# eMMC_SD.net
KiCad netlist of a schematic drawn in Altium Designer
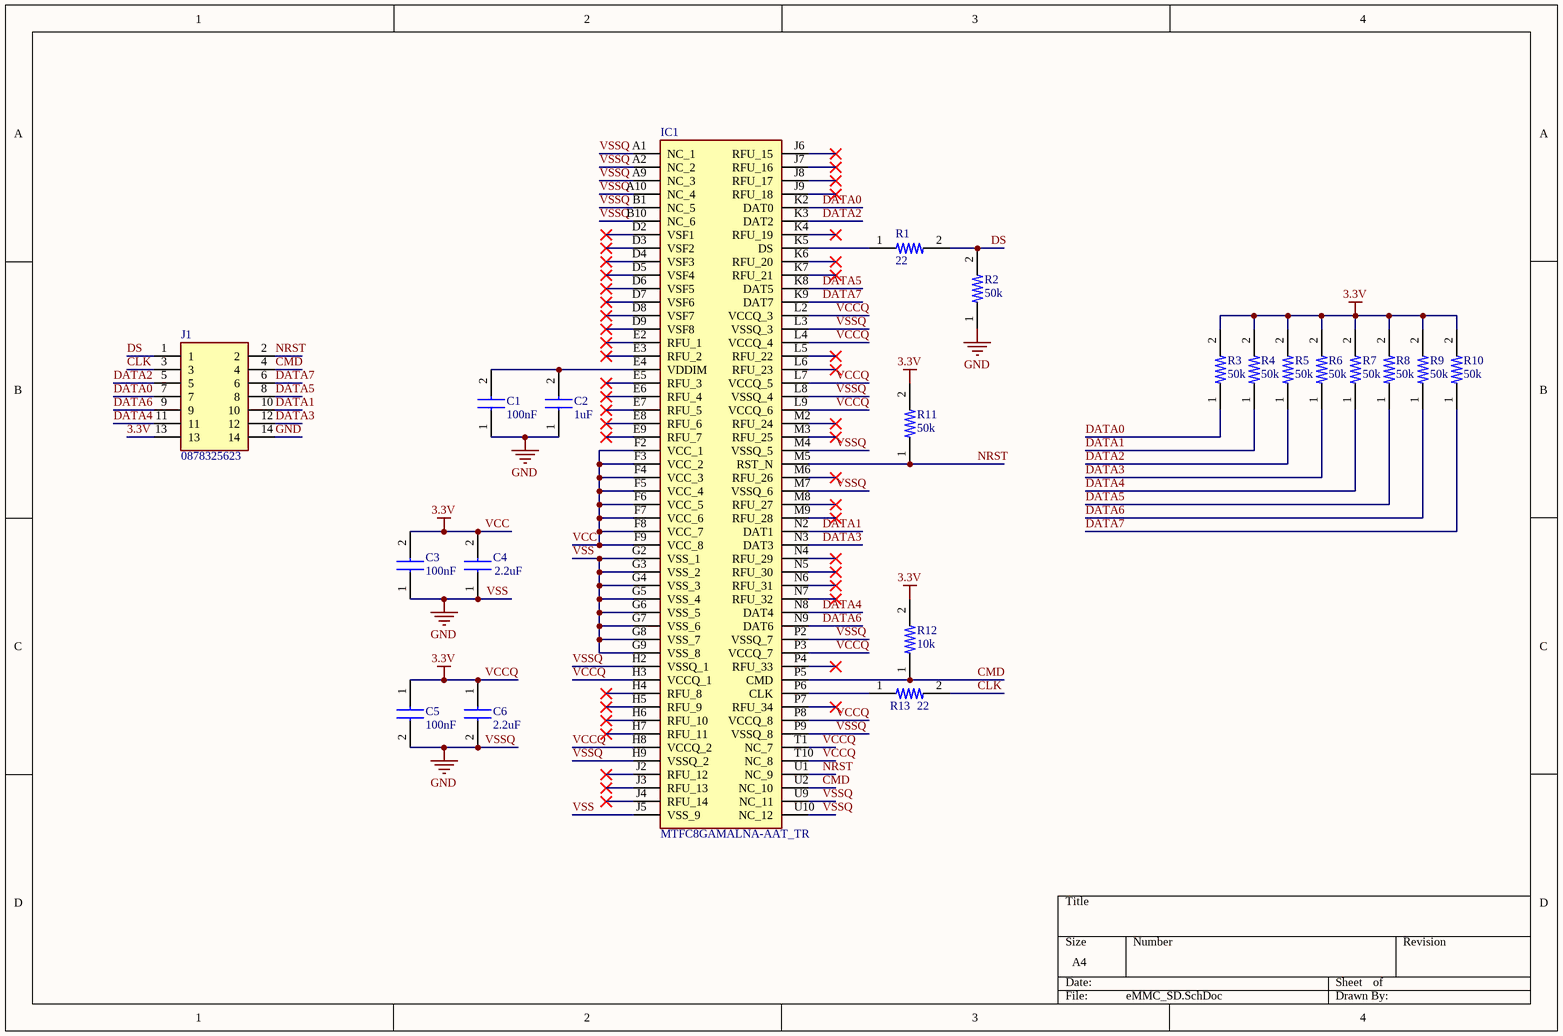
[diagram p0: eMMC_SD.SchDoc]

(export (version "E")
  (design (tool "Eeschema 10.0.6"))
  (components
    (comp (ref "C1")
      (value "100nF")
      (footprint "CAPC2012X140N")
      (description "Capacitor\r\n\r\nKAM21BR71H104JT")
      (fields
        (field (name "MANUFACTURER_PART_NUMBER") "08055C105K4Z2A")
        (field (name "MOUSER PART NUMBER") "581-08055C105K4Z2A")
      )
      (libsource (lib "TLMoto - Eletrónica") (part "MCAST21GSB7105MTNB25"))
    )
    (comp (ref "C2")
      (value "1uF")
      (footprint "CAPC2012X140N")
      (description "Capacitor\r\n\r\n08055C105K4Z2A")
      (fields
        (field (name "MANUFACTURER_PART_NUMBER") "08055C105K4Z2A")
        (field (name "MOUSER PART NUMBER") "581-08055C105K4Z2A")
      )
      (libsource (lib "TLMoto - Eletrónica") (part "MCAST21GSB7105MTNB25"))
    )
    (comp (ref "C3")
      (value "100nF")
      (footprint "CAPC2012X140N")
      (description "Capacitor\r\n\r\nKAM21BR71H104JT")
      (fields
        (field (name "MANUFACTURER_PART_NUMBER") "08055C105K4Z2A")
        (field (name "MOUSER PART NUMBER") "581-08055C105K4Z2A")
      )
      (libsource (lib "TLMoto - Eletrónica") (part "MCAST21GSB7105MTNB25"))
    )
    (comp (ref "C4")
      (value "2.2uF")
      (footprint "CAPC2012X140N")
      (description "Capacitor\r\n\r\nC2012X7R1E225K125AB")
      (fields
        (field (name "MANUFACTURER_PART_NUMBER") "08055C105K4Z2A")
        (field (name "MOUSER PART NUMBER") "581-08055C105K4Z2A")
      )
      (libsource (lib "TLMoto - Eletrónica") (part "MCAST21GSB7105MTNB25"))
    )
    (comp (ref "C5")
      (value "100nF")
      (footprint "CAPC2012X140N")
      (description "Capacitor\r\n\r\nKAM21BR71H104JT")
      (fields
        (field (name "MANUFACTURER_PART_NUMBER") "08055C105K4Z2A")
        (field (name "MOUSER PART NUMBER") "581-08055C105K4Z2A")
      )
      (libsource (lib "TLMoto - Eletrónica") (part "MCAST21GSB7105MTNB25"))
    )
    (comp (ref "C6")
      (value "2.2uF")
      (footprint "CAPC2012X140N")
      (description "Capacitor\r\n\r\nC2012X7R1E225K125AB")
      (fields
        (field (name "MANUFACTURER_PART_NUMBER") "08055C105K4Z2A")
        (field (name "MOUSER PART NUMBER") "581-08055C105K4Z2A")
      )
      (libsource (lib "TLMoto - Eletrónica") (part "MCAST21GSB7105MTNB25"))
    )
    (comp (ref "IC1")
      (value "MTFC8GAMALNA-AAT_TR")
      (footprint "BGA100C100P10X17_1400X1800X120")
      (description "Multi Media Card Controller and NAND Flash e.MMC Memory")
      (fields
        (field (name "MANUFACTURER_PART_NUMBER") "MTFC8GAMALNA-AAT TR")
        (field (name "MOUSER PART NUMBER") "340-354324-REEL")
      )
      (libsource (lib "TLMoto - Eletrónica") (part "MTFC8GAMALNA-AAT_TR"))
    )
    (comp (ref "J1")
      (value "0878325623")
      (footprint "SamacSys:0878325623")
      (description "Connector")
      (libsource (lib "*") (part "0878325623"))
    )
    (comp (ref "R1")
      (value "22")
      (footprint "RESC2012X60N")
      (description "Resistor")
      (fields (field (name "SOURCE") "MotoLibrary.SchLib"))
      (libsource (lib "TLMoto - Eletrónica") (part "R 0805 (2012)"))
    )
    (comp (ref "R2")
      (value "50k")
      (footprint "RESC2012X60N")
      (description "Resistor")
      (fields (field (name "SOURCE") "MotoLibrary.SchLib"))
      (libsource (lib "TLMoto - Eletrónica") (part "R 0805 (2012)"))
    )
    (comp (ref "R3")
      (value "50k")
      (footprint "RESC2012X60N")
      (description "Resistor")
      (fields (field (name "SOURCE") "MotoLibrary.SchLib"))
      (libsource (lib "TLMoto - Eletrónica") (part "R 0805 (2012)"))
    )
    (comp (ref "R4")
      (value "50k")
      (footprint "RESC2012X60N")
      (description "Resistor")
      (fields (field (name "SOURCE") "MotoLibrary.SchLib"))
      (libsource (lib "TLMoto - Eletrónica") (part "R 0805 (2012)"))
    )
    (comp (ref "R5")
      (value "50k")
      (footprint "RESC2012X60N")
      (description "Resistor")
      (fields (field (name "SOURCE") "MotoLibrary.SchLib"))
      (libsource (lib "TLMoto - Eletrónica") (part "R 0805 (2012)"))
    )
    (comp (ref "R6")
      (value "50k")
      (footprint "RESC2012X60N")
      (description "Resistor")
      (fields (field (name "SOURCE") "MotoLibrary.SchLib"))
      (libsource (lib "TLMoto - Eletrónica") (part "R 0805 (2012)"))
    )
    (comp (ref "R7")
      (value "50k")
      (footprint "RESC2012X60N")
      (description "Resistor")
      (fields (field (name "SOURCE") "MotoLibrary.SchLib"))
      (libsource (lib "TLMoto - Eletrónica") (part "R 0805 (2012)"))
    )
    (comp (ref "R8")
      (value "50k")
      (footprint "RESC2012X60N")
      (description "Resistor")
      (fields (field (name "SOURCE") "MotoLibrary.SchLib"))
      (libsource (lib "TLMoto - Eletrónica") (part "R 0805 (2012)"))
    )
    (comp (ref "R9")
      (value "50k")
      (footprint "RESC2012X60N")
      (description "Resistor")
      (fields (field (name "SOURCE") "MotoLibrary.SchLib"))
      (libsource (lib "TLMoto - Eletrónica") (part "R 0805 (2012)"))
    )
    (comp (ref "R10")
      (value "50k")
      (footprint "RESC2012X60N")
      (description "Resistor")
      (fields (field (name "SOURCE") "MotoLibrary.SchLib"))
      (libsource (lib "TLMoto - Eletrónica") (part "R 0805 (2012)"))
    )
    (comp (ref "R11")
      (value "50k")
      (footprint "RESC2012X60N")
      (description "Resistor")
      (fields (field (name "SOURCE") "MotoLibrary.SchLib"))
      (libsource (lib "TLMoto - Eletrónica") (part "R 0805 (2012)"))
    )
    (comp (ref "R12")
      (value "10k")
      (footprint "RESC2012X60N")
      (description "Resistor")
      (fields (field (name "SOURCE") "MotoLibrary.SchLib"))
      (libsource (lib "TLMoto - Eletrónica") (part "R 0805 (2012)"))
    )
    (comp (ref "R13")
      (value "22")
      (footprint "RESC2012X60N")
      (description "Resistor")
      (fields (field (name "SOURCE") "MotoLibrary.SchLib"))
      (libsource (lib "TLMoto - Eletrónica") (part "R 0805 (2012)"))
    )
  )
  (nets
    (net (code "1") (name "/CLK") (class "Default")
      (node (ref "J1") (pin "3") (pinfunction "3_3") (pintype "passive"))
      (node (ref "R13") (pin "2") (pinfunction "2_2") (pintype "passive"))
    )
    (net (code "2") (name "/CMD") (class "Default")
      (node (ref "IC1") (pin "P5") (pinfunction "CMD_P5") (pintype "passive"))
      (node (ref "IC1") (pin "U2") (pinfunction "NC_10_U2") (pintype "passive"))
      (node (ref "J1") (pin "4") (pinfunction "4_4") (pintype "passive"))
      (node (ref "R12") (pin "1") (pinfunction "1_1") (pintype "passive"))
    )
    (net (code "3") (name "/DATA0") (class "Default")
      (node (ref "IC1") (pin "K2") (pinfunction "DAT0_K2") (pintype "passive"))
      (node (ref "J1") (pin "7") (pinfunction "7_7") (pintype "passive"))
      (node (ref "R3") (pin "1") (pinfunction "1_1") (pintype "passive"))
    )
    (net (code "4") (name "/DATA1") (class "Default")
      (node (ref "IC1") (pin "N2") (pinfunction "DAT1_N2") (pintype "passive"))
      (node (ref "J1") (pin "10") (pinfunction "10_10") (pintype "passive"))
      (node (ref "R4") (pin "1") (pinfunction "1_1") (pintype "passive"))
    )
    (net (code "5") (name "/DATA2") (class "Default")
      (node (ref "IC1") (pin "K3") (pinfunction "DAT2_K3") (pintype "passive"))
      (node (ref "J1") (pin "5") (pinfunction "5_5") (pintype "passive"))
      (node (ref "R5") (pin "1") (pinfunction "1_1") (pintype "passive"))
    )
    (net (code "6") (name "/DATA3") (class "Default")
      (node (ref "IC1") (pin "N3") (pinfunction "DAT3_N3") (pintype "passive"))
      (node (ref "J1") (pin "12") (pinfunction "12_12") (pintype "passive"))
      (node (ref "R6") (pin "1") (pinfunction "1_1") (pintype "passive"))
    )
    (net (code "7") (name "/DATA4") (class "Default")
      (node (ref "IC1") (pin "N8") (pinfunction "DAT4_N8") (pintype "passive"))
      (node (ref "J1") (pin "11") (pinfunction "11_11") (pintype "passive"))
      (node (ref "R7") (pin "1") (pinfunction "1_1") (pintype "passive"))
    )
    (net (code "8") (name "/DATA5") (class "Default")
      (node (ref "IC1") (pin "K8") (pinfunction "DAT5_K8") (pintype "passive"))
      (node (ref "J1") (pin "8") (pinfunction "8_8") (pintype "passive"))
      (node (ref "R8") (pin "1") (pinfunction "1_1") (pintype "passive"))
    )
    (net (code "9") (name "/DATA6") (class "Default")
      (node (ref "IC1") (pin "N9") (pinfunction "DAT6_N9") (pintype "passive"))
      (node (ref "J1") (pin "9") (pinfunction "9_9") (pintype "passive"))
      (node (ref "R9") (pin "1") (pinfunction "1_1") (pintype "passive"))
    )
    (net (code "10") (name "/DATA7") (class "Default")
      (node (ref "IC1") (pin "K9") (pinfunction "DAT7_K9") (pintype "passive"))
      (node (ref "J1") (pin "6") (pinfunction "6_6") (pintype "passive"))
      (node (ref "R10") (pin "1") (pinfunction "1_1") (pintype "passive"))
    )
    (net (code "11") (name "/DS") (class "Default")
      (node (ref "J1") (pin "1") (pinfunction "1_1") (pintype "passive"))
      (node (ref "R1") (pin "2") (pinfunction "2_2") (pintype "passive"))
      (node (ref "R2") (pin "2") (pinfunction "2_2") (pintype "passive"))
    )
    (net (code "12") (name "/NRST") (class "Default")
      (node (ref "IC1") (pin "M5") (pinfunction "RST_N_M5") (pintype "passive"))
      (node (ref "IC1") (pin "U1") (pinfunction "NC_9_U1") (pintype "passive"))
      (node (ref "J1") (pin "2") (pinfunction "2_2") (pintype "passive"))
      (node (ref "R11") (pin "1") (pinfunction "1_1") (pintype "passive"))
    )
    (net (code "13") (name "3.3V") (class "Default")
      (node (ref "C3") (pin "2") (pinfunction "2_2") (pintype "passive"))
      (node (ref "C4") (pin "2") (pinfunction "2_2") (pintype "passive"))
      (node (ref "C5") (pin "1") (pinfunction "1_1") (pintype "passive"))
      (node (ref "C6") (pin "1") (pinfunction "1_1") (pintype "passive"))
      (node (ref "IC1") (pin "F2") (pinfunction "VCC_1_F2") (pintype "passive"))
      (node (ref "IC1") (pin "F3") (pinfunction "VCC_2_F3") (pintype "passive"))
      (node (ref "IC1") (pin "F4") (pinfunction "VCC_3_F4") (pintype "passive"))
      (node (ref "IC1") (pin "F5") (pinfunction "VCC_4_F5") (pintype "passive"))
      (node (ref "IC1") (pin "F6") (pinfunction "VCC_5_F6") (pintype "passive"))
      (node (ref "IC1") (pin "F7") (pinfunction "VCC_6_F7") (pintype "passive"))
      (node (ref "IC1") (pin "F8") (pinfunction "VCC_7_F8") (pintype "passive"))
      (node (ref "IC1") (pin "F9") (pinfunction "VCC_8_F9") (pintype "passive"))
      (node (ref "IC1") (pin "H3") (pinfunction "VCCQ_1_H3") (pintype "passive"))
      (node (ref "IC1") (pin "H8") (pinfunction "VCCQ_2_H8") (pintype "passive"))
      (node (ref "IC1") (pin "L2") (pinfunction "VCCQ_3_L2") (pintype "passive"))
      (node (ref "IC1") (pin "L4") (pinfunction "VCCQ_4_L4") (pintype "passive"))
      (node (ref "IC1") (pin "L7") (pinfunction "VCCQ_5_L7") (pintype "passive"))
      (node (ref "IC1") (pin "L9") (pinfunction "VCCQ_6_L9") (pintype "passive"))
      (node (ref "IC1") (pin "P3") (pinfunction "VCCQ_7_P3") (pintype "passive"))
      (node (ref "IC1") (pin "P8") (pinfunction "VCCQ_8_P8") (pintype "passive"))
      (node (ref "IC1") (pin "T1") (pinfunction "NC_7_T1") (pintype "passive"))
      (node (ref "IC1") (pin "T10") (pinfunction "NC_8_T10") (pintype "passive"))
      (node (ref "J1") (pin "13") (pinfunction "13_13") (pintype "passive"))
      (node (ref "R10") (pin "2") (pinfunction "2_2") (pintype "passive"))
      (node (ref "R11") (pin "2") (pinfunction "2_2") (pintype "passive"))
      (node (ref "R12") (pin "2") (pinfunction "2_2") (pintype "passive"))
      (node (ref "R3") (pin "2") (pinfunction "2_2") (pintype "passive"))
      (node (ref "R4") (pin "2") (pinfunction "2_2") (pintype "passive"))
      (node (ref "R5") (pin "2") (pinfunction "2_2") (pintype "passive"))
      (node (ref "R6") (pin "2") (pinfunction "2_2") (pintype "passive"))
      (node (ref "R7") (pin "2") (pinfunction "2_2") (pintype "passive"))
      (node (ref "R8") (pin "2") (pinfunction "2_2") (pintype "passive"))
      (node (ref "R9") (pin "2") (pinfunction "2_2") (pintype "passive"))
    )
    (net (code "14") (name "GND") (class "Default")
      (node (ref "C1") (pin "1") (pinfunction "1_1") (pintype "passive"))
      (node (ref "C2") (pin "1") (pinfunction "1_1") (pintype "passive"))
      (node (ref "C3") (pin "1") (pinfunction "1_1") (pintype "passive"))
      (node (ref "C4") (pin "1") (pinfunction "1_1") (pintype "passive"))
      (node (ref "C5") (pin "2") (pinfunction "2_2") (pintype "passive"))
      (node (ref "C6") (pin "2") (pinfunction "2_2") (pintype "passive"))
      (node (ref "IC1") (pin "A1") (pinfunction "NC_1_A1") (pintype "passive"))
      (node (ref "IC1") (pin "A10") (pinfunction "NC_4_A10") (pintype "passive"))
      (node (ref "IC1") (pin "A2") (pinfunction "NC_2_A2") (pintype "passive"))
      (node (ref "IC1") (pin "A9") (pinfunction "NC_3_A9") (pintype "passive"))
      (node (ref "IC1") (pin "B1") (pinfunction "NC_5_B1") (pintype "passive"))
      (node (ref "IC1") (pin "B10") (pinfunction "NC_6_B10") (pintype "passive"))
      (node (ref "IC1") (pin "G2") (pinfunction "VSS_1_G2") (pintype "passive"))
      (node (ref "IC1") (pin "G3") (pinfunction "VSS_2_G3") (pintype "passive"))
      (node (ref "IC1") (pin "G4") (pinfunction "VSS_3_G4") (pintype "passive"))
      (node (ref "IC1") (pin "G5") (pinfunction "VSS_4_G5") (pintype "passive"))
      (node (ref "IC1") (pin "G6") (pinfunction "VSS_5_G6") (pintype "passive"))
      (node (ref "IC1") (pin "G7") (pinfunction "VSS_6_G7") (pintype "passive"))
      (node (ref "IC1") (pin "G8") (pinfunction "VSS_7_G8") (pintype "passive"))
      (node (ref "IC1") (pin "G9") (pinfunction "VSS_8_G9") (pintype "passive"))
      (node (ref "IC1") (pin "H2") (pinfunction "VSSQ_1_H2") (pintype "passive"))
      (node (ref "IC1") (pin "H9") (pinfunction "VSSQ_2_H9") (pintype "passive"))
      (node (ref "IC1") (pin "J5") (pinfunction "VSS_9_J5") (pintype "passive"))
      (node (ref "IC1") (pin "L3") (pinfunction "VSSQ_3_L3") (pintype "passive"))
      (node (ref "IC1") (pin "L8") (pinfunction "VSSQ_4_L8") (pintype "passive"))
      (node (ref "IC1") (pin "M4") (pinfunction "VSSQ_5_M4") (pintype "passive"))
      (node (ref "IC1") (pin "M7") (pinfunction "VSSQ_6_M7") (pintype "passive"))
      (node (ref "IC1") (pin "P2") (pinfunction "VSSQ_7_P2") (pintype "passive"))
      (node (ref "IC1") (pin "P9") (pinfunction "VSSQ_8_P9") (pintype "passive"))
      (node (ref "IC1") (pin "U10") (pinfunction "NC_12_U10") (pintype "passive"))
      (node (ref "IC1") (pin "U9") (pinfunction "NC_11_U9") (pintype "passive"))
      (node (ref "J1") (pin "14") (pinfunction "14_14") (pintype "passive"))
      (node (ref "R2") (pin "1") (pinfunction "1_1") (pintype "passive"))
    )
    (net (code "15") (name "Net-(IC1-CLK)") (class "Default")
      (node (ref "IC1") (pin "P6") (pinfunction "CLK_P6") (pintype "passive"))
      (node (ref "R13") (pin "1") (pinfunction "1_1") (pintype "passive"))
    )
    (net (code "16") (name "Net-(IC1-DS)") (class "Default")
      (node (ref "IC1") (pin "K5") (pinfunction "DS_K5") (pintype "passive"))
      (node (ref "R1") (pin "1") (pinfunction "1_1") (pintype "passive"))
    )
    (net (code "17") (name "Net-(IC1-VDDIM)") (class "Default")
      (node (ref "C1") (pin "2") (pinfunction "2_2") (pintype "passive"))
      (node (ref "C2") (pin "2") (pinfunction "2_2") (pintype "passive"))
      (node (ref "IC1") (pin "E4") (pinfunction "VDDIM_E4") (pintype "passive"))
    )
    (net (code "18") (name "unconnected-(IC1-RFU_1-PadE2)") (class "Default")
      (node (ref "IC1") (pin "E2") (pinfunction "RFU_1_E2") (pintype "passive+no_connect"))
    )
    (net (code "19") (name "unconnected-(IC1-RFU_2-PadE3)") (class "Default")
      (node (ref "IC1") (pin "E3") (pinfunction "RFU_2_E3") (pintype "passive+no_connect"))
    )
    (net (code "20") (name "unconnected-(IC1-RFU_3-PadE5)") (class "Default")
      (node (ref "IC1") (pin "E5") (pinfunction "RFU_3_E5") (pintype "passive+no_connect"))
    )
    (net (code "21") (name "unconnected-(IC1-RFU_4-PadE6)") (class "Default")
      (node (ref "IC1") (pin "E6") (pinfunction "RFU_4_E6") (pintype "passive+no_connect"))
    )
    (net (code "22") (name "unconnected-(IC1-RFU_5-PadE7)") (class "Default")
      (node (ref "IC1") (pin "E7") (pinfunction "RFU_5_E7") (pintype "passive+no_connect"))
    )
    (net (code "23") (name "unconnected-(IC1-RFU_6-PadE8)") (class "Default")
      (node (ref "IC1") (pin "E8") (pinfunction "RFU_6_E8") (pintype "passive+no_connect"))
    )
    (net (code "24") (name "unconnected-(IC1-RFU_7-PadE9)") (class "Default")
      (node (ref "IC1") (pin "E9") (pinfunction "RFU_7_E9") (pintype "passive+no_connect"))
    )
    (net (code "25") (name "unconnected-(IC1-RFU_8-PadH4)") (class "Default")
      (node (ref "IC1") (pin "H4") (pinfunction "RFU_8_H4") (pintype "passive+no_connect"))
    )
    (net (code "26") (name "unconnected-(IC1-RFU_9-PadH5)") (class "Default")
      (node (ref "IC1") (pin "H5") (pinfunction "RFU_9_H5") (pintype "passive+no_connect"))
    )
    (net (code "27") (name "unconnected-(IC1-RFU_10-PadH6)") (class "Default")
      (node (ref "IC1") (pin "H6") (pinfunction "RFU_10_H6") (pintype "passive+no_connect"))
    )
    (net (code "28") (name "unconnected-(IC1-RFU_11-PadH7)") (class "Default")
      (node (ref "IC1") (pin "H7") (pinfunction "RFU_11_H7") (pintype "passive+no_connect"))
    )
    (net (code "29") (name "unconnected-(IC1-RFU_12-PadJ2)") (class "Default")
      (node (ref "IC1") (pin "J2") (pinfunction "RFU_12_J2") (pintype "passive+no_connect"))
    )
    (net (code "30") (name "unconnected-(IC1-RFU_13-PadJ3)") (class "Default")
      (node (ref "IC1") (pin "J3") (pinfunction "RFU_13_J3") (pintype "passive+no_connect"))
    )
    (net (code "31") (name "unconnected-(IC1-RFU_14-PadJ4)") (class "Default")
      (node (ref "IC1") (pin "J4") (pinfunction "RFU_14_J4") (pintype "passive+no_connect"))
    )
    (net (code "32") (name "unconnected-(IC1-RFU_15-PadJ6)") (class "Default")
      (node (ref "IC1") (pin "J6") (pinfunction "RFU_15_J6") (pintype "passive+no_connect"))
    )
    (net (code "33") (name "unconnected-(IC1-RFU_16-PadJ7)") (class "Default")
      (node (ref "IC1") (pin "J7") (pinfunction "RFU_16_J7") (pintype "passive+no_connect"))
    )
    (net (code "34") (name "unconnected-(IC1-RFU_17-PadJ8)") (class "Default")
      (node (ref "IC1") (pin "J8") (pinfunction "RFU_17_J8") (pintype "passive+no_connect"))
    )
    (net (code "35") (name "unconnected-(IC1-RFU_18-PadJ9)") (class "Default")
      (node (ref "IC1") (pin "J9") (pinfunction "RFU_18_J9") (pintype "passive+no_connect"))
    )
    (net (code "36") (name "unconnected-(IC1-RFU_19-PadK4)") (class "Default")
      (node (ref "IC1") (pin "K4") (pinfunction "RFU_19_K4") (pintype "passive+no_connect"))
    )
    (net (code "37") (name "unconnected-(IC1-RFU_20-PadK6)") (class "Default")
      (node (ref "IC1") (pin "K6") (pinfunction "RFU_20_K6") (pintype "passive+no_connect"))
    )
    (net (code "38") (name "unconnected-(IC1-RFU_21-PadK7)") (class "Default")
      (node (ref "IC1") (pin "K7") (pinfunction "RFU_21_K7") (pintype "passive+no_connect"))
    )
    (net (code "39") (name "unconnected-(IC1-RFU_22-PadL5)") (class "Default")
      (node (ref "IC1") (pin "L5") (pinfunction "RFU_22_L5") (pintype "passive+no_connect"))
    )
    (net (code "40") (name "unconnected-(IC1-RFU_23-PadL6)") (class "Default")
      (node (ref "IC1") (pin "L6") (pinfunction "RFU_23_L6") (pintype "passive+no_connect"))
    )
    (net (code "41") (name "unconnected-(IC1-RFU_24-PadM2)") (class "Default")
      (node (ref "IC1") (pin "M2") (pinfunction "RFU_24_M2") (pintype "passive+no_connect"))
    )
    (net (code "42") (name "unconnected-(IC1-RFU_25-PadM3)") (class "Default")
      (node (ref "IC1") (pin "M3") (pinfunction "RFU_25_M3") (pintype "passive+no_connect"))
    )
    (net (code "43") (name "unconnected-(IC1-RFU_26-PadM6)") (class "Default")
      (node (ref "IC1") (pin "M6") (pinfunction "RFU_26_M6") (pintype "passive+no_connect"))
    )
    (net (code "44") (name "unconnected-(IC1-RFU_27-PadM8)") (class "Default")
      (node (ref "IC1") (pin "M8") (pinfunction "RFU_27_M8") (pintype "passive+no_connect"))
    )
    (net (code "45") (name "unconnected-(IC1-RFU_28-PadM9)") (class "Default")
      (node (ref "IC1") (pin "M9") (pinfunction "RFU_28_M9") (pintype "passive+no_connect"))
    )
    (net (code "46") (name "unconnected-(IC1-RFU_29-PadN4)") (class "Default")
      (node (ref "IC1") (pin "N4") (pinfunction "RFU_29_N4") (pintype "passive+no_connect"))
    )
    (net (code "47") (name "unconnected-(IC1-RFU_30-PadN5)") (class "Default")
      (node (ref "IC1") (pin "N5") (pinfunction "RFU_30_N5") (pintype "passive+no_connect"))
    )
    (net (code "48") (name "unconnected-(IC1-RFU_31-PadN6)") (class "Default")
      (node (ref "IC1") (pin "N6") (pinfunction "RFU_31_N6") (pintype "passive+no_connect"))
    )
    (net (code "49") (name "unconnected-(IC1-RFU_32-PadN7)") (class "Default")
      (node (ref "IC1") (pin "N7") (pinfunction "RFU_32_N7") (pintype "passive+no_connect"))
    )
    (net (code "50") (name "unconnected-(IC1-RFU_33-PadP4)") (class "Default")
      (node (ref "IC1") (pin "P4") (pinfunction "RFU_33_P4") (pintype "passive+no_connect"))
    )
    (net (code "51") (name "unconnected-(IC1-RFU_34-PadP7)") (class "Default")
      (node (ref "IC1") (pin "P7") (pinfunction "RFU_34_P7") (pintype "passive+no_connect"))
    )
    (net (code "52") (name "unconnected-(IC1-VSF1-PadD2)") (class "Default")
      (node (ref "IC1") (pin "D2") (pinfunction "VSF1_D2") (pintype "passive+no_connect"))
    )
    (net (code "53") (name "unconnected-(IC1-VSF2-PadD3)") (class "Default")
      (node (ref "IC1") (pin "D3") (pinfunction "VSF2_D3") (pintype "passive+no_connect"))
    )
    (net (code "54") (name "unconnected-(IC1-VSF3-PadD4)") (class "Default")
      (node (ref "IC1") (pin "D4") (pinfunction "VSF3_D4") (pintype "passive+no_connect"))
    )
    (net (code "55") (name "unconnected-(IC1-VSF4-PadD5)") (class "Default")
      (node (ref "IC1") (pin "D5") (pinfunction "VSF4_D5") (pintype "passive+no_connect"))
    )
    (net (code "56") (name "unconnected-(IC1-VSF5-PadD6)") (class "Default")
      (node (ref "IC1") (pin "D6") (pinfunction "VSF5_D6") (pintype "passive+no_connect"))
    )
    (net (code "57") (name "unconnected-(IC1-VSF6-PadD7)") (class "Default")
      (node (ref "IC1") (pin "D7") (pinfunction "VSF6_D7") (pintype "passive+no_connect"))
    )
    (net (code "58") (name "unconnected-(IC1-VSF7-PadD8)") (class "Default")
      (node (ref "IC1") (pin "D8") (pinfunction "VSF7_D8") (pintype "passive+no_connect"))
    )
    (net (code "59") (name "unconnected-(IC1-VSF8-PadD9)") (class "Default")
      (node (ref "IC1") (pin "D9") (pinfunction "VSF8_D9") (pintype "passive+no_connect"))
    )
  )
)
